# memory.net
KiCad netlist of a schematic drawn in EAGLE
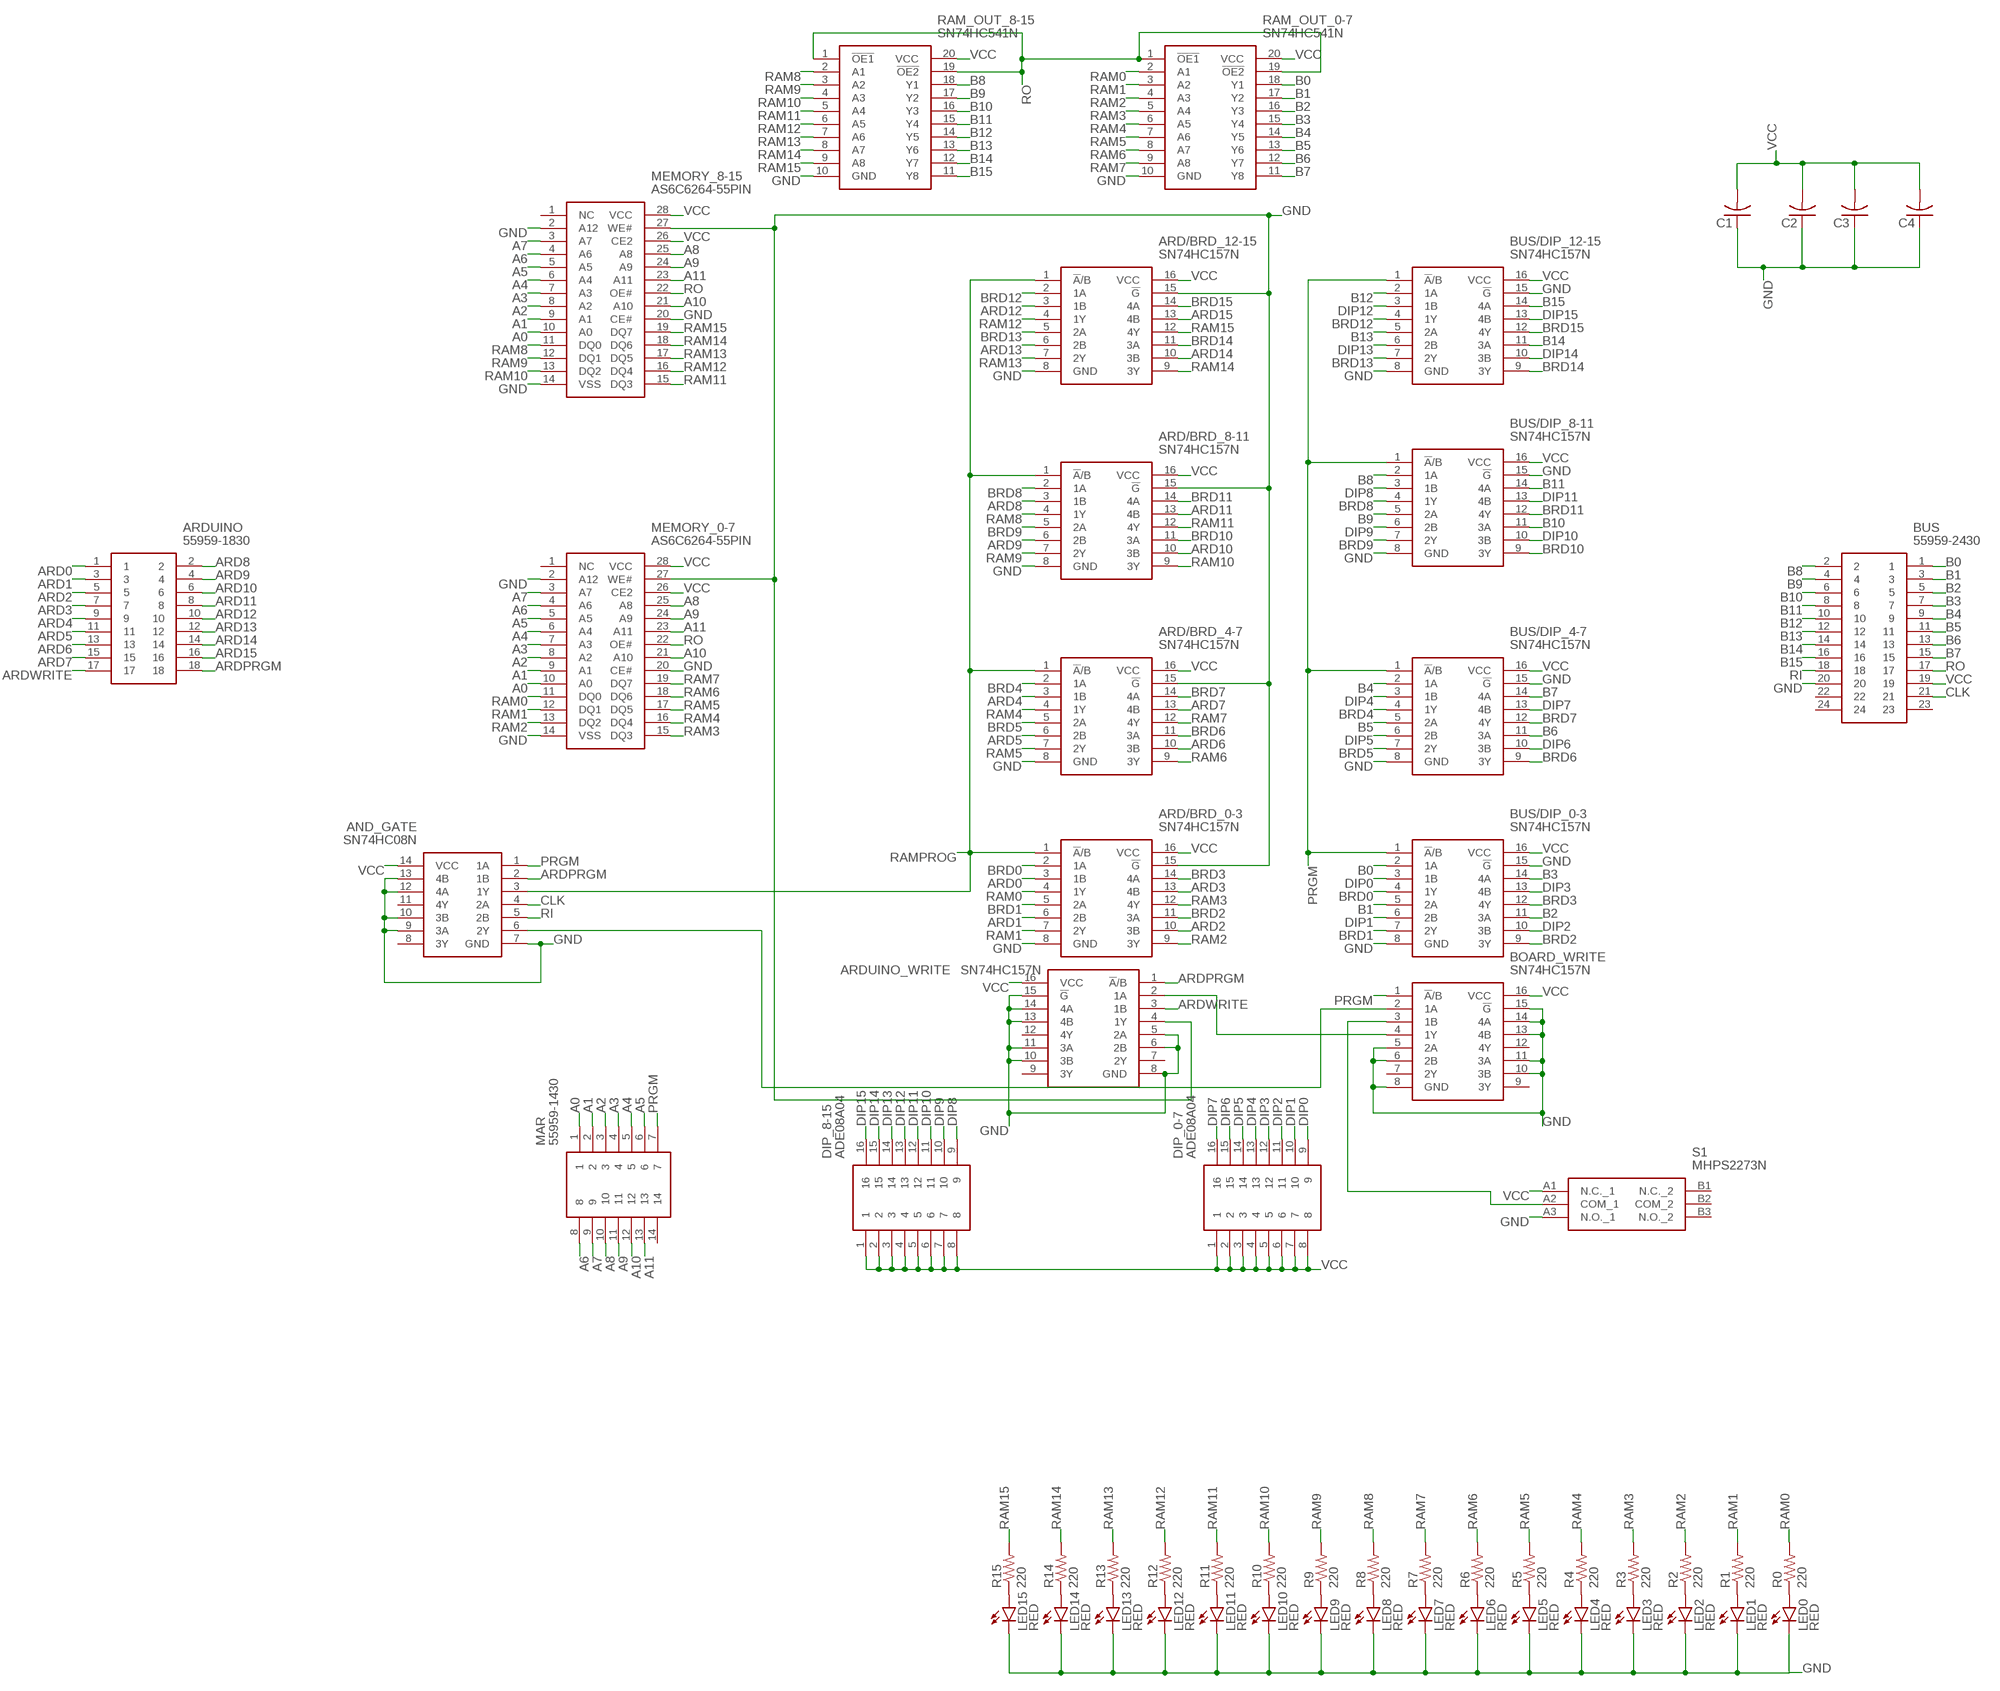
[diagram p0: schematic, sheet 1]

(export (version "E")
  (design (tool "Eeschema 10.0.6"))
  (components
    (comp (ref "AND_GATE")
      (value "SN74HC08N")
      (footprint "eagle-import:DIP794W53P254L1930H508Q14N")
      (fields (field (name "MOUSER_PART_NUMBER") "595-SN74HC08N"))
      (libsource (lib "eagle-import") (part "SN74HC08N"))
    )
    (comp (ref "ARD/BRD_0-3")
      (value "SN74HC157N")
      (footprint "eagle-import:DIP794W53P254L1930H508Q16N")
      (fields (field (name "MOUSER_PART_NUMBER") "595-SN74HC157N"))
      (libsource (lib "eagle-import") (part "SN74HC157N"))
    )
    (comp (ref "ARD/BRD_4-7")
      (value "SN74HC157N")
      (footprint "eagle-import:DIP794W53P254L1930H508Q16N")
      (fields (field (name "MOUSER_PART_NUMBER") "595-SN74HC157N"))
      (libsource (lib "eagle-import") (part "SN74HC157N"))
    )
    (comp (ref "ARD/BRD_8-11")
      (value "SN74HC157N")
      (footprint "eagle-import:DIP794W53P254L1930H508Q16N")
      (fields (field (name "MOUSER_PART_NUMBER") "595-SN74HC157N"))
      (libsource (lib "eagle-import") (part "SN74HC157N"))
    )
    (comp (ref "ARD/BRD_12-15")
      (value "SN74HC157N")
      (footprint "eagle-import:DIP794W53P254L1930H508Q16N")
      (fields (field (name "MOUSER_PART_NUMBER") "595-SN74HC157N"))
      (libsource (lib "eagle-import") (part "SN74HC157N"))
    )
    (comp (ref "ARDUINO")
      (value "55959-1830")
      (footprint "eagle-import:SHDR18W65P250X200_2X9_2140X140")
      (fields (field (name "MOUSER_PART_NUMBER") "538-55959-1830"))
      (libsource (lib "eagle-import") (part "55959-1830"))
    )
    (comp (ref "ARDUINO_WRITE")
      (value "SN74HC157N")
      (footprint "eagle-import:DIP794W53P254L1930H508Q16N")
      (fields (field (name "MOUSER_PART_NUMBER") "595-SN74HC157N"))
      (libsource (lib "eagle-import") (part "SN74HC157N"))
    )
    (comp (ref "BOARD_WRITE")
      (value "SN74HC157N")
      (footprint "eagle-import:DIP794W53P254L1930H508Q16N")
      (fields (field (name "MOUSER_PART_NUMBER") "595-SN74HC157N"))
      (libsource (lib "eagle-import") (part "SN74HC157N"))
    )
    (comp (ref "BUS")
      (value "55959-2430")
      (footprint "eagle-import:559592430")
      (fields (field (name "MOUSER_PART_NUMBER") "538-55959-2430"))
      (libsource (lib "eagle-import") (part "55959-2430"))
    )
    (comp (ref "BUS/DIP_0-3")
      (value "SN74HC157N")
      (footprint "eagle-import:DIP794W53P254L1930H508Q16N")
      (fields (field (name "MOUSER_PART_NUMBER") "595-SN74HC157N"))
      (libsource (lib "eagle-import") (part "SN74HC157N"))
    )
    (comp (ref "BUS/DIP_4-7")
      (value "SN74HC157N")
      (footprint "eagle-import:DIP794W53P254L1930H508Q16N")
      (fields (field (name "MOUSER_PART_NUMBER") "595-SN74HC157N"))
      (libsource (lib "eagle-import") (part "SN74HC157N"))
    )
    (comp (ref "BUS/DIP_8-11")
      (value "SN74HC157N")
      (footprint "eagle-import:DIP794W53P254L1930H508Q16N")
      (fields (field (name "MOUSER_PART_NUMBER") "595-SN74HC157N"))
      (libsource (lib "eagle-import") (part "SN74HC157N"))
    )
    (comp (ref "BUS/DIP_12-15")
      (value "SN74HC157N")
      (footprint "eagle-import:DIP794W53P254L1930H508Q16N")
      (fields (field (name "MOUSER_PART_NUMBER") "595-SN74HC157N"))
      (libsource (lib "eagle-import") (part "SN74HC157N"))
    )
    (comp (ref "C1")
      (value "C-US025-024X044")
      (footprint "eagle-import:C025-024X044")
      (libsource (lib "eagle-import") (part "C-US025-024X044"))
    )
    (comp (ref "C2")
      (value "C-US025-024X044")
      (footprint "eagle-import:C025-024X044")
      (libsource (lib "eagle-import") (part "C-US025-024X044"))
    )
    (comp (ref "C3")
      (value "C-US025-024X044")
      (footprint "eagle-import:C025-024X044")
      (libsource (lib "eagle-import") (part "C-US025-024X044"))
    )
    (comp (ref "C4")
      (value "C-US025-024X044")
      (footprint "eagle-import:C025-024X044")
      (libsource (lib "eagle-import") (part "C-US025-024X044"))
    )
    (comp (ref "DIP_0-7")
      (value "ADE08A04")
      (footprint "eagle-import:DIP810W60P254L2225H590Q16N")
      (fields (field (name "MOUSER_PART_NUMBER") "506-ADE08A04"))
      (libsource (lib "eagle-import") (part "ADE08A04"))
    )
    (comp (ref "DIP_8-15")
      (value "ADE08A04")
      (footprint "eagle-import:DIP810W60P254L2225H590Q16N")
      (fields (field (name "MOUSER_PART_NUMBER") "506-ADE08A04"))
      (libsource (lib "eagle-import") (part "ADE08A04"))
    )
    (comp (ref "LED0")
      (value "RED")
      (footprint "eagle-import:LED3MM")
      (libsource (lib "eagle-import") (part "LED3MM"))
    )
    (comp (ref "LED1")
      (value "RED")
      (footprint "eagle-import:LED3MM")
      (libsource (lib "eagle-import") (part "LED3MM"))
    )
    (comp (ref "LED2")
      (value "RED")
      (footprint "eagle-import:LED3MM")
      (libsource (lib "eagle-import") (part "LED3MM"))
    )
    (comp (ref "LED3")
      (value "RED")
      (footprint "eagle-import:LED3MM")
      (libsource (lib "eagle-import") (part "LED3MM"))
    )
    (comp (ref "LED4")
      (value "RED")
      (footprint "eagle-import:LED3MM")
      (libsource (lib "eagle-import") (part "LED3MM"))
    )
    (comp (ref "LED5")
      (value "RED")
      (footprint "eagle-import:LED3MM")
      (libsource (lib "eagle-import") (part "LED3MM"))
    )
    (comp (ref "LED6")
      (value "RED")
      (footprint "eagle-import:LED3MM")
      (libsource (lib "eagle-import") (part "LED3MM"))
    )
    (comp (ref "LED7")
      (value "RED")
      (footprint "eagle-import:LED3MM")
      (libsource (lib "eagle-import") (part "LED3MM"))
    )
    (comp (ref "LED8")
      (value "RED")
      (footprint "eagle-import:LED3MM")
      (libsource (lib "eagle-import") (part "LED3MM"))
    )
    (comp (ref "LED9")
      (value "RED")
      (footprint "eagle-import:LED3MM")
      (libsource (lib "eagle-import") (part "LED3MM"))
    )
    (comp (ref "LED10")
      (value "RED")
      (footprint "eagle-import:LED3MM")
      (libsource (lib "eagle-import") (part "LED3MM"))
    )
    (comp (ref "LED11")
      (value "RED")
      (footprint "eagle-import:LED3MM")
      (libsource (lib "eagle-import") (part "LED3MM"))
    )
    (comp (ref "LED12")
      (value "RED")
      (footprint "eagle-import:LED3MM")
      (libsource (lib "eagle-import") (part "LED3MM"))
    )
    (comp (ref "LED13")
      (value "RED")
      (footprint "eagle-import:LED3MM")
      (libsource (lib "eagle-import") (part "LED3MM"))
    )
    (comp (ref "LED14")
      (value "RED")
      (footprint "eagle-import:LED3MM")
      (libsource (lib "eagle-import") (part "LED3MM"))
    )
    (comp (ref "LED15")
      (value "RED")
      (footprint "eagle-import:LED3MM")
      (libsource (lib "eagle-import") (part "LED3MM"))
    )
    (comp (ref "MAR")
      (value "55959-1430")
      (footprint "eagle-import:559591430")
      (fields (field (name "MOUSER_PART_NUMBER") "538-55959-1430"))
      (libsource (lib "eagle-import") (part "55959-1430"))
    )
    (comp (ref "MEMORY_0-7")
      (value "AS6C6264-55PIN")
      (footprint "eagle-import:DIP1524W51P254L3632H394Q28N")
      (fields (field (name "MOUSER_PART_NUMBER") "913-AS6C6264-55PIN"))
      (libsource (lib "eagle-import") (part "AS6C6264-55PIN"))
    )
    (comp (ref "MEMORY_8-15")
      (value "AS6C6264-55PIN")
      (footprint "eagle-import:DIP1524W51P254L3632H394Q28N")
      (fields (field (name "MOUSER_PART_NUMBER") "913-AS6C6264-55PIN"))
      (libsource (lib "eagle-import") (part "AS6C6264-55PIN"))
    )
    (comp (ref "R0")
      (value "220")
      (footprint "eagle-import:0204_7")
      (libsource (lib "eagle-import") (part "R-US_0204/7"))
    )
    (comp (ref "R1")
      (value "220")
      (footprint "eagle-import:0204_7")
      (libsource (lib "eagle-import") (part "R-US_0204/7"))
    )
    (comp (ref "R2")
      (value "220")
      (footprint "eagle-import:0204_7")
      (libsource (lib "eagle-import") (part "R-US_0204/7"))
    )
    (comp (ref "R3")
      (value "220")
      (footprint "eagle-import:0204_7")
      (libsource (lib "eagle-import") (part "R-US_0204/7"))
    )
    (comp (ref "R4")
      (value "220")
      (footprint "eagle-import:0204_7")
      (libsource (lib "eagle-import") (part "R-US_0204/7"))
    )
    (comp (ref "R5")
      (value "220")
      (footprint "eagle-import:0204_7")
      (libsource (lib "eagle-import") (part "R-US_0204/7"))
    )
    (comp (ref "R6")
      (value "220")
      (footprint "eagle-import:0204_7")
      (libsource (lib "eagle-import") (part "R-US_0204/7"))
    )
    (comp (ref "R7")
      (value "220")
      (footprint "eagle-import:0204_7")
      (libsource (lib "eagle-import") (part "R-US_0204/7"))
    )
    (comp (ref "R8")
      (value "220")
      (footprint "eagle-import:0204_7")
      (libsource (lib "eagle-import") (part "R-US_0204/7"))
    )
    (comp (ref "R9")
      (value "220")
      (footprint "eagle-import:0204_7")
      (libsource (lib "eagle-import") (part "R-US_0204/7"))
    )
    (comp (ref "R10")
      (value "220")
      (footprint "eagle-import:0204_7")
      (libsource (lib "eagle-import") (part "R-US_0204/7"))
    )
    (comp (ref "R11")
      (value "220")
      (footprint "eagle-import:0204_7")
      (libsource (lib "eagle-import") (part "R-US_0204/7"))
    )
    (comp (ref "R12")
      (value "220")
      (footprint "eagle-import:0204_7")
      (libsource (lib "eagle-import") (part "R-US_0204/7"))
    )
    (comp (ref "R13")
      (value "220")
      (footprint "eagle-import:0204_7")
      (libsource (lib "eagle-import") (part "R-US_0204/7"))
    )
    (comp (ref "R14")
      (value "220")
      (footprint "eagle-import:0204_7")
      (libsource (lib "eagle-import") (part "R-US_0204/7"))
    )
    (comp (ref "R15")
      (value "220")
      (footprint "eagle-import:0204_7")
      (libsource (lib "eagle-import") (part "R-US_0204/7"))
    )
    (comp (ref "RAM_OUT_0-7")
      (value "SN74HC541N")
      (footprint "eagle-import:DIP794W53P254L2540H508Q20N")
      (fields (field (name "MOUSER_PART_NUMBER") "595-SN74HC541N"))
      (libsource (lib "eagle-import") (part "SN74HC541N"))
    )
    (comp (ref "RAM_OUT_8-15")
      (value "SN74HC541N")
      (footprint "eagle-import:DIP794W53P254L2540H508Q20N")
      (fields (field (name "MOUSER_PART_NUMBER") "595-SN74HC541N"))
      (libsource (lib "eagle-import") (part "SN74HC541N"))
    )
    (comp (ref "S1")
      (value "MHPS2273N")
      (footprint "eagle-import:MHPS2273N")
      (fields (field (name "MOUSER_PART_NUMBER") "642-MHPS2273N"))
      (libsource (lib "eagle-import") (part "MHPS2273N"))
    )
  )
  (nets
    (net (code "1") (name "/A0") (class "Default")
      (node (ref "MAR") (pin "1") (pinfunction "1_1") (pintype "bidirectional"))
      (node (ref "MEMORY_0-7") (pin "10") (pinfunction "A0_10") (pintype "bidirectional"))
      (node (ref "MEMORY_8-15") (pin "10") (pinfunction "A0_10") (pintype "bidirectional"))
    )
    (net (code "2") (name "/A1") (class "Default")
      (node (ref "MAR") (pin "2") (pinfunction "2_2") (pintype "bidirectional"))
      (node (ref "MEMORY_0-7") (pin "9") (pinfunction "A1_9") (pintype "bidirectional"))
      (node (ref "MEMORY_8-15") (pin "9") (pinfunction "A1_9") (pintype "bidirectional"))
    )
    (net (code "3") (name "/A2") (class "Default")
      (node (ref "MAR") (pin "3") (pinfunction "3_3") (pintype "bidirectional"))
      (node (ref "MEMORY_0-7") (pin "8") (pinfunction "A2_8") (pintype "bidirectional"))
      (node (ref "MEMORY_8-15") (pin "8") (pinfunction "A2_8") (pintype "bidirectional"))
    )
    (net (code "4") (name "/A3") (class "Default")
      (node (ref "MAR") (pin "4") (pinfunction "4_4") (pintype "bidirectional"))
      (node (ref "MEMORY_0-7") (pin "7") (pinfunction "A3_7") (pintype "bidirectional"))
      (node (ref "MEMORY_8-15") (pin "7") (pinfunction "A3_7") (pintype "bidirectional"))
    )
    (net (code "5") (name "/A4") (class "Default")
      (node (ref "MAR") (pin "5") (pinfunction "5_5") (pintype "bidirectional"))
      (node (ref "MEMORY_0-7") (pin "6") (pinfunction "A4_6") (pintype "bidirectional"))
      (node (ref "MEMORY_8-15") (pin "6") (pinfunction "A4_6") (pintype "bidirectional"))
    )
    (net (code "6") (name "/A5") (class "Default")
      (node (ref "MAR") (pin "6") (pinfunction "6_6") (pintype "bidirectional"))
      (node (ref "MEMORY_0-7") (pin "5") (pinfunction "A5_5") (pintype "bidirectional"))
      (node (ref "MEMORY_8-15") (pin "5") (pinfunction "A5_5") (pintype "bidirectional"))
    )
    (net (code "7") (name "/A6") (class "Default")
      (node (ref "MAR") (pin "8") (pinfunction "8_8") (pintype "bidirectional"))
      (node (ref "MEMORY_0-7") (pin "4") (pinfunction "A6_4") (pintype "bidirectional"))
      (node (ref "MEMORY_8-15") (pin "4") (pinfunction "A6_4") (pintype "bidirectional"))
    )
    (net (code "8") (name "/A7") (class "Default")
      (node (ref "MAR") (pin "9") (pinfunction "9_9") (pintype "bidirectional"))
      (node (ref "MEMORY_0-7") (pin "3") (pinfunction "A7_3") (pintype "bidirectional"))
      (node (ref "MEMORY_8-15") (pin "3") (pinfunction "A7_3") (pintype "bidirectional"))
    )
    (net (code "9") (name "/A8") (class "Default")
      (node (ref "MAR") (pin "10") (pinfunction "10_10") (pintype "bidirectional"))
      (node (ref "MEMORY_0-7") (pin "25") (pinfunction "A8_25") (pintype "bidirectional"))
      (node (ref "MEMORY_8-15") (pin "25") (pinfunction "A8_25") (pintype "bidirectional"))
    )
    (net (code "10") (name "/A9") (class "Default")
      (node (ref "MAR") (pin "11") (pinfunction "11_11") (pintype "bidirectional"))
      (node (ref "MEMORY_0-7") (pin "24") (pinfunction "A9_24") (pintype "bidirectional"))
      (node (ref "MEMORY_8-15") (pin "24") (pinfunction "A9_24") (pintype "bidirectional"))
    )
    (net (code "11") (name "/A10") (class "Default")
      (node (ref "MAR") (pin "12") (pinfunction "12_12") (pintype "bidirectional"))
      (node (ref "MEMORY_0-7") (pin "21") (pinfunction "A10_21") (pintype "bidirectional"))
      (node (ref "MEMORY_8-15") (pin "21") (pinfunction "A10_21") (pintype "bidirectional"))
    )
    (net (code "12") (name "/A11") (class "Default")
      (node (ref "MAR") (pin "13") (pinfunction "13_13") (pintype "bidirectional"))
      (node (ref "MEMORY_0-7") (pin "23") (pinfunction "A11_23") (pintype "bidirectional"))
      (node (ref "MEMORY_8-15") (pin "23") (pinfunction "A11_23") (pintype "bidirectional"))
    )
    (net (code "13") (name "/ARD0") (class "Default")
      (node (ref "ARD/BRD_0-3") (pin "3") (pinfunction "1B_3") (pintype "bidirectional"))
      (node (ref "ARDUINO") (pin "1") (pinfunction "1_1") (pintype "bidirectional"))
    )
    (net (code "14") (name "/ARD1") (class "Default")
      (node (ref "ARD/BRD_0-3") (pin "6") (pinfunction "2B_6") (pintype "bidirectional"))
      (node (ref "ARDUINO") (pin "3") (pinfunction "3_3") (pintype "bidirectional"))
    )
    (net (code "15") (name "/ARD2") (class "Default")
      (node (ref "ARD/BRD_0-3") (pin "10") (pinfunction "3B_10") (pintype "bidirectional"))
      (node (ref "ARDUINO") (pin "5") (pinfunction "5_5") (pintype "bidirectional"))
    )
    (net (code "16") (name "/ARD3") (class "Default")
      (node (ref "ARD/BRD_0-3") (pin "13") (pinfunction "4B_13") (pintype "bidirectional"))
      (node (ref "ARDUINO") (pin "7") (pinfunction "7_7") (pintype "bidirectional"))
    )
    (net (code "17") (name "/ARD4") (class "Default")
      (node (ref "ARD/BRD_4-7") (pin "3") (pinfunction "1B_3") (pintype "bidirectional"))
      (node (ref "ARDUINO") (pin "9") (pinfunction "9_9") (pintype "bidirectional"))
    )
    (net (code "18") (name "/ARD5") (class "Default")
      (node (ref "ARD/BRD_4-7") (pin "6") (pinfunction "2B_6") (pintype "bidirectional"))
      (node (ref "ARDUINO") (pin "11") (pinfunction "11_11") (pintype "bidirectional"))
    )
    (net (code "19") (name "/ARD6") (class "Default")
      (node (ref "ARD/BRD_4-7") (pin "10") (pinfunction "3B_10") (pintype "bidirectional"))
      (node (ref "ARDUINO") (pin "13") (pinfunction "13_13") (pintype "bidirectional"))
    )
    (net (code "20") (name "/ARD7") (class "Default")
      (node (ref "ARD/BRD_4-7") (pin "13") (pinfunction "4B_13") (pintype "bidirectional"))
      (node (ref "ARDUINO") (pin "15") (pinfunction "15_15") (pintype "bidirectional"))
    )
    (net (code "21") (name "/ARD8") (class "Default")
      (node (ref "ARD/BRD_8-11") (pin "3") (pinfunction "1B_3") (pintype "bidirectional"))
      (node (ref "ARDUINO") (pin "2") (pinfunction "2_2") (pintype "bidirectional"))
    )
    (net (code "22") (name "/ARD9") (class "Default")
      (node (ref "ARD/BRD_8-11") (pin "6") (pinfunction "2B_6") (pintype "bidirectional"))
      (node (ref "ARDUINO") (pin "4") (pinfunction "4_4") (pintype "bidirectional"))
    )
    (net (code "23") (name "/ARD10") (class "Default")
      (node (ref "ARD/BRD_8-11") (pin "10") (pinfunction "3B_10") (pintype "bidirectional"))
      (node (ref "ARDUINO") (pin "6") (pinfunction "6_6") (pintype "bidirectional"))
    )
    (net (code "24") (name "/ARD11") (class "Default")
      (node (ref "ARD/BRD_8-11") (pin "13") (pinfunction "4B_13") (pintype "bidirectional"))
      (node (ref "ARDUINO") (pin "8") (pinfunction "8_8") (pintype "bidirectional"))
    )
    (net (code "25") (name "/ARD12") (class "Default")
      (node (ref "ARD/BRD_12-15") (pin "3") (pinfunction "1B_3") (pintype "bidirectional"))
      (node (ref "ARDUINO") (pin "10") (pinfunction "10_10") (pintype "bidirectional"))
    )
    (net (code "26") (name "/ARD13") (class "Default")
      (node (ref "ARD/BRD_12-15") (pin "6") (pinfunction "2B_6") (pintype "bidirectional"))
      (node (ref "ARDUINO") (pin "12") (pinfunction "12_12") (pintype "bidirectional"))
    )
    (net (code "27") (name "/ARD14") (class "Default")
      (node (ref "ARD/BRD_12-15") (pin "10") (pinfunction "3B_10") (pintype "bidirectional"))
      (node (ref "ARDUINO") (pin "14") (pinfunction "14_14") (pintype "bidirectional"))
    )
    (net (code "28") (name "/ARD15") (class "Default")
      (node (ref "ARD/BRD_12-15") (pin "13") (pinfunction "4B_13") (pintype "bidirectional"))
      (node (ref "ARDUINO") (pin "16") (pinfunction "16_16") (pintype "bidirectional"))
    )
    (net (code "29") (name "/ARDPRGM") (class "Default")
      (node (ref "AND_GATE") (pin "2") (pinfunction "1B_2") (pintype "bidirectional"))
      (node (ref "ARDUINO") (pin "18") (pinfunction "18_18") (pintype "bidirectional"))
      (node (ref "ARDUINO_WRITE") (pin "1") (pinfunction "~{A}/B_1") (pintype "bidirectional"))
    )
    (net (code "30") (name "/ARDWRITE") (class "Default")
      (node (ref "ARDUINO") (pin "17") (pinfunction "17_17") (pintype "bidirectional"))
      (node (ref "ARDUINO_WRITE") (pin "3") (pinfunction "1B_3") (pintype "bidirectional"))
    )
    (net (code "31") (name "/B0") (class "Default")
      (node (ref "BUS") (pin "1") (pinfunction "1_1") (pintype "bidirectional"))
      (node (ref "BUS/DIP_0-3") (pin "2") (pinfunction "1A_2") (pintype "bidirectional"))
      (node (ref "RAM_OUT_0-7") (pin "18") (pinfunction "Y1_18") (pintype "bidirectional"))
    )
    (net (code "32") (name "/B1") (class "Default")
      (node (ref "BUS") (pin "3") (pinfunction "3_3") (pintype "bidirectional"))
      (node (ref "BUS/DIP_0-3") (pin "5") (pinfunction "2A_5") (pintype "bidirectional"))
      (node (ref "RAM_OUT_0-7") (pin "17") (pinfunction "Y2_17") (pintype "bidirectional"))
    )
    (net (code "33") (name "/B2") (class "Default")
      (node (ref "BUS") (pin "5") (pinfunction "5_5") (pintype "bidirectional"))
      (node (ref "BUS/DIP_0-3") (pin "11") (pinfunction "3A_11") (pintype "bidirectional"))
      (node (ref "RAM_OUT_0-7") (pin "16") (pinfunction "Y3_16") (pintype "bidirectional"))
    )
    (net (code "34") (name "/B3") (class "Default")
      (node (ref "BUS") (pin "7") (pinfunction "7_7") (pintype "bidirectional"))
      (node (ref "BUS/DIP_0-3") (pin "14") (pinfunction "4A_14") (pintype "bidirectional"))
      (node (ref "RAM_OUT_0-7") (pin "15") (pinfunction "Y4_15") (pintype "bidirectional"))
    )
    (net (code "35") (name "/B4") (class "Default")
      (node (ref "BUS") (pin "9") (pinfunction "9_9") (pintype "bidirectional"))
      (node (ref "BUS/DIP_4-7") (pin "2") (pinfunction "1A_2") (pintype "bidirectional"))
      (node (ref "RAM_OUT_0-7") (pin "14") (pinfunction "Y5_14") (pintype "bidirectional"))
    )
    (net (code "36") (name "/B5") (class "Default")
      (node (ref "BUS") (pin "11") (pinfunction "11_11") (pintype "bidirectional"))
      (node (ref "BUS/DIP_4-7") (pin "5") (pinfunction "2A_5") (pintype "bidirectional"))
      (node (ref "RAM_OUT_0-7") (pin "13") (pinfunction "Y6_13") (pintype "bidirectional"))
    )
    (net (code "37") (name "/B6") (class "Default")
      (node (ref "BUS") (pin "13") (pinfunction "13_13") (pintype "bidirectional"))
      (node (ref "BUS/DIP_4-7") (pin "11") (pinfunction "3A_11") (pintype "bidirectional"))
      (node (ref "RAM_OUT_0-7") (pin "12") (pinfunction "Y7_12") (pintype "bidirectional"))
    )
    (net (code "38") (name "/B7") (class "Default")
      (node (ref "BUS") (pin "15") (pinfunction "15_15") (pintype "bidirectional"))
      (node (ref "BUS/DIP_4-7") (pin "14") (pinfunction "4A_14") (pintype "bidirectional"))
      (node (ref "RAM_OUT_0-7") (pin "11") (pinfunction "Y8_11") (pintype "bidirectional"))
    )
    (net (code "39") (name "/B8") (class "Default")
      (node (ref "BUS") (pin "2") (pinfunction "2_2") (pintype "bidirectional"))
      (node (ref "BUS/DIP_8-11") (pin "2") (pinfunction "1A_2") (pintype "bidirectional"))
      (node (ref "RAM_OUT_8-15") (pin "18") (pinfunction "Y1_18") (pintype "bidirectional"))
    )
    (net (code "40") (name "/B9") (class "Default")
      (node (ref "BUS") (pin "4") (pinfunction "4_4") (pintype "bidirectional"))
      (node (ref "BUS/DIP_8-11") (pin "5") (pinfunction "2A_5") (pintype "bidirectional"))
      (node (ref "RAM_OUT_8-15") (pin "17") (pinfunction "Y2_17") (pintype "bidirectional"))
    )
    (net (code "41") (name "/B10") (class "Default")
      (node (ref "BUS") (pin "6") (pinfunction "6_6") (pintype "bidirectional"))
      (node (ref "BUS/DIP_8-11") (pin "11") (pinfunction "3A_11") (pintype "bidirectional"))
      (node (ref "RAM_OUT_8-15") (pin "16") (pinfunction "Y3_16") (pintype "bidirectional"))
    )
    (net (code "42") (name "/B11") (class "Default")
      (node (ref "BUS") (pin "8") (pinfunction "8_8") (pintype "bidirectional"))
      (node (ref "BUS/DIP_8-11") (pin "14") (pinfunction "4A_14") (pintype "bidirectional"))
      (node (ref "RAM_OUT_8-15") (pin "15") (pinfunction "Y4_15") (pintype "bidirectional"))
    )
    (net (code "43") (name "/B12") (class "Default")
      (node (ref "BUS") (pin "10") (pinfunction "10_10") (pintype "bidirectional"))
      (node (ref "BUS/DIP_12-15") (pin "2") (pinfunction "1A_2") (pintype "bidirectional"))
      (node (ref "RAM_OUT_8-15") (pin "14") (pinfunction "Y5_14") (pintype "bidirectional"))
    )
    (net (code "44") (name "/B13") (class "Default")
      (node (ref "BUS") (pin "12") (pinfunction "12_12") (pintype "bidirectional"))
      (node (ref "BUS/DIP_12-15") (pin "5") (pinfunction "2A_5") (pintype "bidirectional"))
      (node (ref "RAM_OUT_8-15") (pin "13") (pinfunction "Y6_13") (pintype "bidirectional"))
    )
    (net (code "45") (name "/B14") (class "Default")
      (node (ref "BUS") (pin "14") (pinfunction "14_14") (pintype "bidirectional"))
      (node (ref "BUS/DIP_12-15") (pin "11") (pinfunction "3A_11") (pintype "bidirectional"))
      (node (ref "RAM_OUT_8-15") (pin "12") (pinfunction "Y7_12") (pintype "bidirectional"))
    )
    (net (code "46") (name "/B15") (class "Default")
      (node (ref "BUS") (pin "16") (pinfunction "16_16") (pintype "bidirectional"))
      (node (ref "BUS/DIP_12-15") (pin "14") (pinfunction "4A_14") (pintype "bidirectional"))
      (node (ref "RAM_OUT_8-15") (pin "11") (pinfunction "Y8_11") (pintype "bidirectional"))
    )
    (net (code "47") (name "/BRD0") (class "Default")
      (node (ref "ARD/BRD_0-3") (pin "2") (pinfunction "1A_2") (pintype "bidirectional"))
      (node (ref "BUS/DIP_0-3") (pin "4") (pinfunction "1Y_4") (pintype "bidirectional"))
    )
    (net (code "48") (name "/BRD1") (class "Default")
      (node (ref "ARD/BRD_0-3") (pin "5") (pinfunction "2A_5") (pintype "bidirectional"))
      (node (ref "BUS/DIP_0-3") (pin "7") (pinfunction "2Y_7") (pintype "bidirectional"))
    )
    (net (code "49") (name "/BRD2") (class "Default")
      (node (ref "ARD/BRD_0-3") (pin "11") (pinfunction "3A_11") (pintype "bidirectional"))
      (node (ref "BUS/DIP_0-3") (pin "9") (pinfunction "3Y_9") (pintype "bidirectional"))
    )
    (net (code "50") (name "/BRD3") (class "Default")
      (node (ref "ARD/BRD_0-3") (pin "14") (pinfunction "4A_14") (pintype "bidirectional"))
      (node (ref "BUS/DIP_0-3") (pin "12") (pinfunction "4Y_12") (pintype "bidirectional"))
    )
    (net (code "51") (name "/BRD4") (class "Default")
      (node (ref "ARD/BRD_4-7") (pin "2") (pinfunction "1A_2") (pintype "bidirectional"))
      (node (ref "BUS/DIP_4-7") (pin "4") (pinfunction "1Y_4") (pintype "bidirectional"))
    )
    (net (code "52") (name "/BRD5") (class "Default")
      (node (ref "ARD/BRD_4-7") (pin "5") (pinfunction "2A_5") (pintype "bidirectional"))
      (node (ref "BUS/DIP_4-7") (pin "7") (pinfunction "2Y_7") (pintype "bidirectional"))
    )
    (net (code "53") (name "/BRD6") (class "Default")
      (node (ref "ARD/BRD_4-7") (pin "11") (pinfunction "3A_11") (pintype "bidirectional"))
      (node (ref "BUS/DIP_4-7") (pin "9") (pinfunction "3Y_9") (pintype "bidirectional"))
    )
    (net (code "54") (name "/BRD7") (class "Default")
      (node (ref "ARD/BRD_4-7") (pin "14") (pinfunction "4A_14") (pintype "bidirectional"))
      (node (ref "BUS/DIP_4-7") (pin "12") (pinfunction "4Y_12") (pintype "bidirectional"))
    )
    (net (code "55") (name "/BRD8") (class "Default")
      (node (ref "ARD/BRD_8-11") (pin "2") (pinfunction "1A_2") (pintype "bidirectional"))
      (node (ref "BUS/DIP_8-11") (pin "4") (pinfunction "1Y_4") (pintype "bidirectional"))
    )
    (net (code "56") (name "/BRD9") (class "Default")
      (node (ref "ARD/BRD_8-11") (pin "5") (pinfunction "2A_5") (pintype "bidirectional"))
      (node (ref "BUS/DIP_8-11") (pin "7") (pinfunction "2Y_7") (pintype "bidirectional"))
    )
    (net (code "57") (name "/BRD10") (class "Default")
      (node (ref "ARD/BRD_8-11") (pin "11") (pinfunction "3A_11") (pintype "bidirectional"))
      (node (ref "BUS/DIP_8-11") (pin "9") (pinfunction "3Y_9") (pintype "bidirectional"))
    )
    (net (code "58") (name "/BRD11") (class "Default")
      (node (ref "ARD/BRD_8-11") (pin "14") (pinfunction "4A_14") (pintype "bidirectional"))
      (node (ref "BUS/DIP_8-11") (pin "12") (pinfunction "4Y_12") (pintype "bidirectional"))
    )
    (net (code "59") (name "/BRD12") (class "Default")
      (node (ref "ARD/BRD_12-15") (pin "2") (pinfunction "1A_2") (pintype "bidirectional"))
      (node (ref "BUS/DIP_12-15") (pin "4") (pinfunction "1Y_4") (pintype "bidirectional"))
    )
    (net (code "60") (name "/BRD13") (class "Default")
      (node (ref "ARD/BRD_12-15") (pin "5") (pinfunction "2A_5") (pintype "bidirectional"))
      (node (ref "BUS/DIP_12-15") (pin "7") (pinfunction "2Y_7") (pintype "bidirectional"))
    )
    (net (code "61") (name "/BRD14") (class "Default")
      (node (ref "ARD/BRD_12-15") (pin "11") (pinfunction "3A_11") (pintype "bidirectional"))
      (node (ref "BUS/DIP_12-15") (pin "9") (pinfunction "3Y_9") (pintype "bidirectional"))
    )
    (net (code "62") (name "/BRD15") (class "Default")
      (node (ref "ARD/BRD_12-15") (pin "14") (pinfunction "4A_14") (pintype "bidirectional"))
      (node (ref "BUS/DIP_12-15") (pin "12") (pinfunction "4Y_12") (pintype "bidirectional"))
    )
    (net (code "63") (name "/CLK") (class "Default")
      (node (ref "AND_GATE") (pin "4") (pinfunction "2A_4") (pintype "bidirectional"))
      (node (ref "BUS") (pin "21") (pinfunction "21_21") (pintype "bidirectional"))
    )
    (net (code "64") (name "/DIP0") (class "Default")
      (node (ref "BUS/DIP_0-3") (pin "3") (pinfunction "1B_3") (pintype "bidirectional"))
      (node (ref "DIP_0-7") (pin "9") (pinfunction "9_9") (pintype "bidirectional"))
    )
    (net (code "65") (name "/DIP1") (class "Default")
      (node (ref "BUS/DIP_0-3") (pin "6") (pinfunction "2B_6") (pintype "bidirectional"))
      (node (ref "DIP_0-7") (pin "10") (pinfunction "10_10") (pintype "bidirectional"))
    )
    (net (code "66") (name "/DIP2") (class "Default")
      (node (ref "BUS/DIP_0-3") (pin "10") (pinfunction "3B_10") (pintype "bidirectional"))
      (node (ref "DIP_0-7") (pin "11") (pinfunction "11_11") (pintype "bidirectional"))
    )
    (net (code "67") (name "/DIP3") (class "Default")
      (node (ref "BUS/DIP_0-3") (pin "13") (pinfunction "4B_13") (pintype "bidirectional"))
      (node (ref "DIP_0-7") (pin "12") (pinfunction "12_12") (pintype "bidirectional"))
    )
    (net (code "68") (name "/DIP4") (class "Default")
      (node (ref "BUS/DIP_4-7") (pin "3") (pinfunction "1B_3") (pintype "bidirectional"))
      (node (ref "DIP_0-7") (pin "13") (pinfunction "13_13") (pintype "bidirectional"))
    )
    (net (code "69") (name "/DIP5") (class "Default")
      (node (ref "BUS/DIP_4-7") (pin "6") (pinfunction "2B_6") (pintype "bidirectional"))
      (node (ref "DIP_0-7") (pin "14") (pinfunction "14_14") (pintype "bidirectional"))
    )
    (net (code "70") (name "/DIP6") (class "Default")
      (node (ref "BUS/DIP_4-7") (pin "10") (pinfunction "3B_10") (pintype "bidirectional"))
      (node (ref "DIP_0-7") (pin "15") (pinfunction "15_15") (pintype "bidirectional"))
    )
    (net (code "71") (name "/DIP7") (class "Default")
      (node (ref "BUS/DIP_4-7") (pin "13") (pinfunction "4B_13") (pintype "bidirectional"))
      (node (ref "DIP_0-7") (pin "16") (pinfunction "16_16") (pintype "bidirectional"))
    )
    (net (code "72") (name "/DIP8") (class "Default")
      (node (ref "BUS/DIP_8-11") (pin "3") (pinfunction "1B_3") (pintype "bidirectional"))
      (node (ref "DIP_8-15") (pin "9") (pinfunction "9_9") (pintype "bidirectional"))
    )
    (net (code "73") (name "/DIP9") (class "Default")
      (node (ref "BUS/DIP_8-11") (pin "6") (pinfunction "2B_6") (pintype "bidirectional"))
      (node (ref "DIP_8-15") (pin "10") (pinfunction "10_10") (pintype "bidirectional"))
    )
    (net (code "74") (name "/DIP10") (class "Default")
      (node (ref "BUS/DIP_8-11") (pin "10") (pinfunction "3B_10") (pintype "bidirectional"))
      (node (ref "DIP_8-15") (pin "11") (pinfunction "11_11") (pintype "bidirectional"))
    )
    (net (code "75") (name "/DIP11") (class "Default")
      (node (ref "BUS/DIP_8-11") (pin "13") (pinfunction "4B_13") (pintype "bidirectional"))
      (node (ref "DIP_8-15") (pin "12") (pinfunction "12_12") (pintype "bidirectional"))
    )
    (net (code "76") (name "/DIP12") (class "Default")
      (node (ref "BUS/DIP_12-15") (pin "3") (pinfunction "1B_3") (pintype "bidirectional"))
      (node (ref "DIP_8-15") (pin "13") (pinfunction "13_13") (pintype "bidirectional"))
    )
    (net (code "77") (name "/DIP13") (class "Default")
      (node (ref "BUS/DIP_12-15") (pin "6") (pinfunction "2B_6") (pintype "bidirectional"))
      (node (ref "DIP_8-15") (pin "14") (pinfunction "14_14") (pintype "bidirectional"))
    )
    (net (code "78") (name "/DIP14") (class "Default")
      (node (ref "BUS/DIP_12-15") (pin "10") (pinfunction "3B_10") (pintype "bidirectional"))
      (node (ref "DIP_8-15") (pin "15") (pinfunction "15_15") (pintype "bidirectional"))
    )
    (net (code "79") (name "/DIP15") (class "Default")
      (node (ref "BUS/DIP_12-15") (pin "13") (pinfunction "4B_13") (pintype "bidirectional"))
      (node (ref "DIP_8-15") (pin "16") (pinfunction "16_16") (pintype "bidirectional"))
    )
    (net (code "80") (name "/GND") (class "Default")
      (node (ref "AND_GATE") (pin "10") (pinfunction "3B_10") (pintype "bidirectional"))
      (node (ref "AND_GATE") (pin "12") (pinfunction "4A_12") (pintype "bidirectional"))
      (node (ref "AND_GATE") (pin "13") (pinfunction "4B_13") (pintype "bidirectional"))
      (node (ref "AND_GATE") (pin "7") (pinfunction "GND_7") (pintype "bidirectional"))
      (node (ref "AND_GATE") (pin "9") (pinfunction "3A_9") (pintype "bidirectional"))
      (node (ref "ARD/BRD_0-3") (pin "15") (pinfunction "~{G}_15") (pintype "bidirectional"))
      (node (ref "ARD/BRD_0-3") (pin "8") (pinfunction "GND_8") (pintype "bidirectional"))
      (node (ref "ARD/BRD_12-15") (pin "15") (pinfunction "~{G}_15") (pintype "bidirectional"))
      (node (ref "ARD/BRD_12-15") (pin "8") (pinfunction "GND_8") (pintype "bidirectional"))
      (node (ref "ARD/BRD_4-7") (pin "15") (pinfunction "~{G}_15") (pintype "bidirectional"))
      (node (ref "ARD/BRD_4-7") (pin "8") (pinfunction "GND_8") (pintype "bidirectional"))
      (node (ref "ARD/BRD_8-11") (pin "15") (pinfunction "~{G}_15") (pintype "bidirectional"))
      (node (ref "ARD/BRD_8-11") (pin "8") (pinfunction "GND_8") (pintype "bidirectional"))
      (node (ref "ARDUINO_WRITE") (pin "10") (pinfunction "3B_10") (pintype "bidirectional"))
      (node (ref "ARDUINO_WRITE") (pin "11") (pinfunction "3A_11") (pintype "bidirectional"))
      (node (ref "ARDUINO_WRITE") (pin "13") (pinfunction "4B_13") (pintype "bidirectional"))
      (node (ref "ARDUINO_WRITE") (pin "14") (pinfunction "4A_14") (pintype "bidirectional"))
      (node (ref "ARDUINO_WRITE") (pin "15") (pinfunction "~{G}_15") (pintype "bidirectional"))
      (node (ref "ARDUINO_WRITE") (pin "4") (pinfunction "1Y_4") (pintype "bidirectional"))
      (node (ref "ARDUINO_WRITE") (pin "5") (pinfunction "2A_5") (pintype "bidirectional"))
      (node (ref "ARDUINO_WRITE") (pin "6") (pinfunction "2B_6") (pintype "bidirectional"))
      (node (ref "ARDUINO_WRITE") (pin "8") (pinfunction "GND_8") (pintype "bidirectional"))
      (node (ref "BOARD_WRITE") (pin "10") (pinfunction "3B_10") (pintype "bidirectional"))
      (node (ref "BOARD_WRITE") (pin "11") (pinfunction "3A_11") (pintype "bidirectional"))
      (node (ref "BOARD_WRITE") (pin "13") (pinfunction "4B_13") (pintype "bidirectional"))
      (node (ref "BOARD_WRITE") (pin "14") (pinfunction "4A_14") (pintype "bidirectional"))
      (node (ref "BOARD_WRITE") (pin "15") (pinfunction "~{G}_15") (pintype "bidirectional"))
      (node (ref "BOARD_WRITE") (pin "5") (pinfunction "2A_5") (pintype "bidirectional"))
      (node (ref "BOARD_WRITE") (pin "6") (pinfunction "2B_6") (pintype "bidirectional"))
      (node (ref "BOARD_WRITE") (pin "8") (pinfunction "GND_8") (pintype "bidirectional"))
      (node (ref "BUS") (pin "20") (pinfunction "20_20") (pintype "bidirectional"))
      (node (ref "BUS/DIP_0-3") (pin "15") (pinfunction "~{G}_15") (pintype "bidirectional"))
      (node (ref "BUS/DIP_0-3") (pin "8") (pinfunction "GND_8") (pintype "bidirectional"))
      (node (ref "BUS/DIP_12-15") (pin "15") (pinfunction "~{G}_15") (pintype "bidirectional"))
      (node (ref "BUS/DIP_12-15") (pin "8") (pinfunction "GND_8") (pintype "bidirectional"))
      (node (ref "BUS/DIP_4-7") (pin "15") (pinfunction "~{G}_15") (pintype "bidirectional"))
      (node (ref "BUS/DIP_4-7") (pin "8") (pinfunction "GND_8") (pintype "bidirectional"))
      (node (ref "BUS/DIP_8-11") (pin "15") (pinfunction "~{G}_15") (pintype "bidirectional"))
      (node (ref "BUS/DIP_8-11") (pin "8") (pinfunction "GND_8") (pintype "bidirectional"))
      (node (ref "C1") (pin "1") (pinfunction "1_1") (pintype "passive"))
      (node (ref "C2") (pin "1") (pinfunction "1_1") (pintype "passive"))
      (node (ref "C3") (pin "1") (pinfunction "1_1") (pintype "passive"))
      (node (ref "C4") (pin "1") (pinfunction "1_1") (pintype "passive"))
      (node (ref "LED0") (pin "K") (pinfunction "C_K") (pintype "passive"))
      (node (ref "LED1") (pin "K") (pinfunction "C_K") (pintype "passive"))
      (node (ref "LED10") (pin "K") (pinfunction "C_K") (pintype "passive"))
      (node (ref "LED11") (pin "K") (pinfunction "C_K") (pintype "passive"))
      (node (ref "LED12") (pin "K") (pinfunction "C_K") (pintype "passive"))
      (node (ref "LED13") (pin "K") (pinfunction "C_K") (pintype "passive"))
      (node (ref "LED14") (pin "K") (pinfunction "C_K") (pintype "passive"))
      (node (ref "LED15") (pin "K") (pinfunction "C_K") (pintype "passive"))
      (node (ref "LED2") (pin "K") (pinfunction "C_K") (pintype "passive"))
      (node (ref "LED3") (pin "K") (pinfunction "C_K") (pintype "passive"))
      (node (ref "LED4") (pin "K") (pinfunction "C_K") (pintype "passive"))
      (node (ref "LED5") (pin "K") (pinfunction "C_K") (pintype "passive"))
      (node (ref "LED6") (pin "K") (pinfunction "C_K") (pintype "passive"))
      (node (ref "LED7") (pin "K") (pinfunction "C_K") (pintype "passive"))
      (node (ref "LED8") (pin "K") (pinfunction "C_K") (pintype "passive"))
      (node (ref "LED9") (pin "K") (pinfunction "C_K") (pintype "passive"))
      (node (ref "MEMORY_0-7") (pin "14") (pinfunction "VSS_14") (pintype "bidirectional"))
      (node (ref "MEMORY_0-7") (pin "2") (pinfunction "A12_2") (pintype "bidirectional"))
      (node (ref "MEMORY_0-7") (pin "20") (pinfunction "CE#_20") (pintype "bidirectional"))
      (node (ref "MEMORY_0-7") (pin "27") (pinfunction "WE#_27") (pintype "bidirectional"))
      (node (ref "MEMORY_8-15") (pin "14") (pinfunction "VSS_14") (pintype "bidirectional"))
      (node (ref "MEMORY_8-15") (pin "2") (pinfunction "A12_2") (pintype "bidirectional"))
      (node (ref "MEMORY_8-15") (pin "20") (pinfunction "CE#_20") (pintype "bidirectional"))
      (node (ref "MEMORY_8-15") (pin "27") (pinfunction "WE#_27") (pintype "bidirectional"))
      (node (ref "RAM_OUT_0-7") (pin "10") (pinfunction "GND_10") (pintype "bidirectional"))
      (node (ref "RAM_OUT_8-15") (pin "10") (pinfunction "GND_10") (pintype "bidirectional"))
      (node (ref "S1") (pin "A3") (pinfunction "N.O._1_A3") (pintype "bidirectional"))
    )
    (net (code "81") (name "/PRGM") (class "Default")
      (node (ref "AND_GATE") (pin "1") (pinfunction "1A_1") (pintype "bidirectional"))
      (node (ref "BOARD_WRITE") (pin "1") (pinfunction "~{A}/B_1") (pintype "bidirectional"))
      (node (ref "BUS/DIP_0-3") (pin "1") (pinfunction "~{A}/B_1") (pintype "bidirectional"))
      (node (ref "BUS/DIP_12-15") (pin "1") (pinfunction "~{A}/B_1") (pintype "bidirectional"))
      (node (ref "BUS/DIP_4-7") (pin "1") (pinfunction "~{A}/B_1") (pintype "bidirectional"))
      (node (ref "BUS/DIP_8-11") (pin "1") (pinfunction "~{A}/B_1") (pintype "bidirectional"))
      (node (ref "MAR") (pin "7") (pinfunction "7_7") (pintype "bidirectional"))
    )
    (net (code "82") (name "/RAM0") (class "Default")
      (node (ref "ARD/BRD_0-3") (pin "4") (pinfunction "1Y_4") (pintype "bidirectional"))
      (node (ref "MEMORY_0-7") (pin "11") (pinfunction "DQ0_11") (pintype "bidirectional"))
      (node (ref "R0") (pin "2") (pinfunction "2_2") (pintype "passive"))
      (node (ref "RAM_OUT_0-7") (pin "2") (pinfunction "A1_2") (pintype "bidirectional"))
    )
    (net (code "83") (name "/RAM1") (class "Default")
      (node (ref "ARD/BRD_0-3") (pin "7") (pinfunction "2Y_7") (pintype "bidirectional"))
      (node (ref "MEMORY_0-7") (pin "12") (pinfunction "DQ1_12") (pintype "bidirectional"))
      (node (ref "R1") (pin "2") (pinfunction "2_2") (pintype "passive"))
      (node (ref "RAM_OUT_0-7") (pin "3") (pinfunction "A2_3") (pintype "bidirectional"))
    )
    (net (code "84") (name "/RAM2") (class "Default")
      (node (ref "ARD/BRD_0-3") (pin "9") (pinfunction "3Y_9") (pintype "bidirectional"))
      (node (ref "MEMORY_0-7") (pin "13") (pinfunction "DQ2_13") (pintype "bidirectional"))
      (node (ref "R2") (pin "2") (pinfunction "2_2") (pintype "passive"))
      (node (ref "RAM_OUT_0-7") (pin "4") (pinfunction "A3_4") (pintype "bidirectional"))
    )
    (net (code "85") (name "/RAM3") (class "Default")
      (node (ref "ARD/BRD_0-3") (pin "12") (pinfunction "4Y_12") (pintype "bidirectional"))
      (node (ref "MEMORY_0-7") (pin "15") (pinfunction "DQ3_15") (pintype "bidirectional"))
      (node (ref "R3") (pin "2") (pinfunction "2_2") (pintype "passive"))
      (node (ref "RAM_OUT_0-7") (pin "5") (pinfunction "A4_5") (pintype "bidirectional"))
    )
    (net (code "86") (name "/RAM4") (class "Default")
      (node (ref "ARD/BRD_4-7") (pin "4") (pinfunction "1Y_4") (pintype "bidirectional"))
      (node (ref "MEMORY_0-7") (pin "16") (pinfunction "DQ4_16") (pintype "bidirectional"))
      (node (ref "R4") (pin "2") (pinfunction "2_2") (pintype "passive"))
      (node (ref "RAM_OUT_0-7") (pin "6") (pinfunction "A5_6") (pintype "bidirectional"))
    )
    (net (code "87") (name "/RAM5") (class "Default")
      (node (ref "ARD/BRD_4-7") (pin "7") (pinfunction "2Y_7") (pintype "bidirectional"))
      (node (ref "MEMORY_0-7") (pin "17") (pinfunction "DQ5_17") (pintype "bidirectional"))
      (node (ref "R5") (pin "2") (pinfunction "2_2") (pintype "passive"))
      (node (ref "RAM_OUT_0-7") (pin "7") (pinfunction "A6_7") (pintype "bidirectional"))
    )
    (net (code "88") (name "/RAM6") (class "Default")
      (node (ref "ARD/BRD_4-7") (pin "9") (pinfunction "3Y_9") (pintype "bidirectional"))
      (node (ref "MEMORY_0-7") (pin "18") (pinfunction "DQ6_18") (pintype "bidirectional"))
      (node (ref "R6") (pin "2") (pinfunction "2_2") (pintype "passive"))
      (node (ref "RAM_OUT_0-7") (pin "8") (pinfunction "A7_8") (pintype "bidirectional"))
    )
    (net (code "89") (name "/RAM7") (class "Default")
      (node (ref "ARD/BRD_4-7") (pin "12") (pinfunction "4Y_12") (pintype "bidirectional"))
      (node (ref "MEMORY_0-7") (pin "19") (pinfunction "DQ7_19") (pintype "bidirectional"))
      (node (ref "R7") (pin "2") (pinfunction "2_2") (pintype "passive"))
      (node (ref "RAM_OUT_0-7") (pin "9") (pinfunction "A8_9") (pintype "bidirectional"))
    )
    (net (code "90") (name "/RAM8") (class "Default")
      (node (ref "ARD/BRD_8-11") (pin "4") (pinfunction "1Y_4") (pintype "bidirectional"))
      (node (ref "MEMORY_8-15") (pin "11") (pinfunction "DQ0_11") (pintype "bidirectional"))
      (node (ref "R8") (pin "2") (pinfunction "2_2") (pintype "passive"))
      (node (ref "RAM_OUT_8-15") (pin "2") (pinfunction "A1_2") (pintype "bidirectional"))
    )
    (net (code "91") (name "/RAM9") (class "Default")
      (node (ref "ARD/BRD_8-11") (pin "7") (pinfunction "2Y_7") (pintype "bidirectional"))
      (node (ref "MEMORY_8-15") (pin "12") (pinfunction "DQ1_12") (pintype "bidirectional"))
      (node (ref "R9") (pin "2") (pinfunction "2_2") (pintype "passive"))
      (node (ref "RAM_OUT_8-15") (pin "3") (pinfunction "A2_3") (pintype "bidirectional"))
    )
    (net (code "92") (name "/RAM10") (class "Default")
      (node (ref "ARD/BRD_8-11") (pin "9") (pinfunction "3Y_9") (pintype "bidirectional"))
      (node (ref "MEMORY_8-15") (pin "13") (pinfunction "DQ2_13") (pintype "bidirectional"))
      (node (ref "R10") (pin "2") (pinfunction "2_2") (pintype "passive"))
      (node (ref "RAM_OUT_8-15") (pin "4") (pinfunction "A3_4") (pintype "bidirectional"))
    )
    (net (code "93") (name "/RAM11") (class "Default")
      (node (ref "ARD/BRD_8-11") (pin "12") (pinfunction "4Y_12") (pintype "bidirectional"))
      (node (ref "MEMORY_8-15") (pin "15") (pinfunction "DQ3_15") (pintype "bidirectional"))
      (node (ref "R11") (pin "2") (pinfunction "2_2") (pintype "passive"))
      (node (ref "RAM_OUT_8-15") (pin "5") (pinfunction "A4_5") (pintype "bidirectional"))
    )
    (net (code "94") (name "/RAM12") (class "Default")
      (node (ref "ARD/BRD_12-15") (pin "4") (pinfunction "1Y_4") (pintype "bidirectional"))
      (node (ref "MEMORY_8-15") (pin "16") (pinfunction "DQ4_16") (pintype "bidirectional"))
      (node (ref "R12") (pin "2") (pinfunction "2_2") (pintype "passive"))
      (node (ref "RAM_OUT_8-15") (pin "6") (pinfunction "A5_6") (pintype "bidirectional"))
    )
    (net (code "95") (name "/RAM13") (class "Default")
      (node (ref "ARD/BRD_12-15") (pin "7") (pinfunction "2Y_7") (pintype "bidirectional"))
      (node (ref "MEMORY_8-15") (pin "17") (pinfunction "DQ5_17") (pintype "bidirectional"))
      (node (ref "R13") (pin "2") (pinfunction "2_2") (pintype "passive"))
      (node (ref "RAM_OUT_8-15") (pin "7") (pinfunction "A6_7") (pintype "bidirectional"))
    )
    (net (code "96") (name "/RAM14") (class "Default")
      (node (ref "ARD/BRD_12-15") (pin "9") (pinfunction "3Y_9") (pintype "bidirectional"))
      (node (ref "MEMORY_8-15") (pin "18") (pinfunction "DQ6_18") (pintype "bidirectional"))
      (node (ref "R14") (pin "2") (pinfunction "2_2") (pintype "passive"))
      (node (ref "RAM_OUT_8-15") (pin "8") (pinfunction "A7_8") (pintype "bidirectional"))
    )
    (net (code "97") (name "/RAM15") (class "Default")
      (node (ref "ARD/BRD_12-15") (pin "12") (pinfunction "4Y_12") (pintype "bidirectional"))
      (node (ref "MEMORY_8-15") (pin "19") (pinfunction "DQ7_19") (pintype "bidirectional"))
      (node (ref "R15") (pin "2") (pinfunction "2_2") (pintype "passive"))
      (node (ref "RAM_OUT_8-15") (pin "9") (pinfunction "A8_9") (pintype "bidirectional"))
    )
    (net (code "98") (name "/RAMPROG") (class "Default")
      (node (ref "AND_GATE") (pin "3") (pinfunction "1Y_3") (pintype "bidirectional"))
      (node (ref "ARD/BRD_0-3") (pin "1") (pinfunction "~{A}/B_1") (pintype "bidirectional"))
      (node (ref "ARD/BRD_12-15") (pin "1") (pinfunction "~{A}/B_1") (pintype "bidirectional"))
      (node (ref "ARD/BRD_4-7") (pin "1") (pinfunction "~{A}/B_1") (pintype "bidirectional"))
      (node (ref "ARD/BRD_8-11") (pin "1") (pinfunction "~{A}/B_1") (pintype "bidirectional"))
    )
    (net (code "99") (name "/RI") (class "Default")
      (node (ref "AND_GATE") (pin "5") (pinfunction "2B_5") (pintype "bidirectional"))
      (node (ref "BUS") (pin "18") (pinfunction "18_18") (pintype "bidirectional"))
    )
    (net (code "100") (name "/RO") (class "Default")
      (node (ref "BUS") (pin "17") (pinfunction "17_17") (pintype "bidirectional"))
      (node (ref "MEMORY_0-7") (pin "22") (pinfunction "OE#_22") (pintype "bidirectional"))
      (node (ref "MEMORY_8-15") (pin "22") (pinfunction "OE#_22") (pintype "bidirectional"))
      (node (ref "RAM_OUT_0-7") (pin "1") (pinfunction "~{OE1}_1") (pintype "bidirectional"))
      (node (ref "RAM_OUT_0-7") (pin "19") (pinfunction "~{OE2}_19") (pintype "bidirectional"))
      (node (ref "RAM_OUT_8-15") (pin "1") (pinfunction "~{OE1}_1") (pintype "bidirectional"))
      (node (ref "RAM_OUT_8-15") (pin "19") (pinfunction "~{OE2}_19") (pintype "bidirectional"))
    )
    (net (code "101") (name "/VCC") (class "Default")
      (node (ref "AND_GATE") (pin "14") (pinfunction "VCC_14") (pintype "bidirectional"))
      (node (ref "ARD/BRD_0-3") (pin "16") (pinfunction "VCC_16") (pintype "bidirectional"))
      (node (ref "ARD/BRD_12-15") (pin "16") (pinfunction "VCC_16") (pintype "bidirectional"))
      (node (ref "ARD/BRD_4-7") (pin "16") (pinfunction "VCC_16") (pintype "bidirectional"))
      (node (ref "ARD/BRD_8-11") (pin "16") (pinfunction "VCC_16") (pintype "bidirectional"))
      (node (ref "ARDUINO_WRITE") (pin "16") (pinfunction "VCC_16") (pintype "bidirectional"))
      (node (ref "BOARD_WRITE") (pin "16") (pinfunction "VCC_16") (pintype "bidirectional"))
      (node (ref "BUS") (pin "19") (pinfunction "19_19") (pintype "bidirectional"))
      (node (ref "BUS/DIP_0-3") (pin "16") (pinfunction "VCC_16") (pintype "bidirectional"))
      (node (ref "BUS/DIP_12-15") (pin "16") (pinfunction "VCC_16") (pintype "bidirectional"))
      (node (ref "BUS/DIP_4-7") (pin "16") (pinfunction "VCC_16") (pintype "bidirectional"))
      (node (ref "BUS/DIP_8-11") (pin "16") (pinfunction "VCC_16") (pintype "bidirectional"))
      (node (ref "C1") (pin "2") (pinfunction "2_2") (pintype "passive"))
      (node (ref "C2") (pin "2") (pinfunction "2_2") (pintype "passive"))
      (node (ref "C3") (pin "2") (pinfunction "2_2") (pintype "passive"))
      (node (ref "C4") (pin "2") (pinfunction "2_2") (pintype "passive"))
      (node (ref "DIP_0-7") (pin "1") (pinfunction "1_1") (pintype "bidirectional"))
      (node (ref "DIP_0-7") (pin "2") (pinfunction "2_2") (pintype "bidirectional"))
      (node (ref "DIP_0-7") (pin "3") (pinfunction "3_3") (pintype "bidirectional"))
      (node (ref "DIP_0-7") (pin "4") (pinfunction "4_4") (pintype "bidirectional"))
      (node (ref "DIP_0-7") (pin "5") (pinfunction "5_5") (pintype "bidirectional"))
      (node (ref "DIP_0-7") (pin "6") (pinfunction "6_6") (pintype "bidirectional"))
      (node (ref "DIP_0-7") (pin "7") (pinfunction "7_7") (pintype "bidirectional"))
      (node (ref "DIP_0-7") (pin "8") (pinfunction "8_8") (pintype "bidirectional"))
      (node (ref "DIP_8-15") (pin "1") (pinfunction "1_1") (pintype "bidirectional"))
      (node (ref "DIP_8-15") (pin "2") (pinfunction "2_2") (pintype "bidirectional"))
      (node (ref "DIP_8-15") (pin "3") (pinfunction "3_3") (pintype "bidirectional"))
      (node (ref "DIP_8-15") (pin "4") (pinfunction "4_4") (pintype "bidirectional"))
      (node (ref "DIP_8-15") (pin "5") (pinfunction "5_5") (pintype "bidirectional"))
      (node (ref "DIP_8-15") (pin "6") (pinfunction "6_6") (pintype "bidirectional"))
      (node (ref "DIP_8-15") (pin "7") (pinfunction "7_7") (pintype "bidirectional"))
      (node (ref "DIP_8-15") (pin "8") (pinfunction "8_8") (pintype "bidirectional"))
      (node (ref "MEMORY_0-7") (pin "26") (pinfunction "CE2_26") (pintype "bidirectional"))
      (node (ref "MEMORY_0-7") (pin "28") (pinfunction "VCC_28") (pintype "bidirectional"))
      (node (ref "MEMORY_8-15") (pin "26") (pinfunction "CE2_26") (pintype "bidirectional"))
      (node (ref "MEMORY_8-15") (pin "28") (pinfunction "VCC_28") (pintype "bidirectional"))
      (node (ref "RAM_OUT_0-7") (pin "20") (pinfunction "VCC_20") (pintype "bidirectional"))
      (node (ref "RAM_OUT_8-15") (pin "20") (pinfunction "VCC_20") (pintype "bidirectional"))
      (node (ref "S1") (pin "A1") (pinfunction "N.C._1_A1") (pintype "bidirectional"))
    )
    (net (code "102") (name "Net-(AND_GATE-2Y)") (class "Default")
      (node (ref "AND_GATE") (pin "6") (pinfunction "2Y_6") (pintype "bidirectional"))
      (node (ref "BOARD_WRITE") (pin "2") (pinfunction "1A_2") (pintype "bidirectional"))
    )
    (net (code "103") (name "Net-(ARDUINO_WRITE-1A)") (class "Default")
      (node (ref "ARDUINO_WRITE") (pin "2") (pinfunction "1A_2") (pintype "bidirectional"))
      (node (ref "BOARD_WRITE") (pin "4") (pinfunction "1Y_4") (pintype "bidirectional"))
    )
    (net (code "104") (name "Net-(BOARD_WRITE-1B)") (class "Default")
      (node (ref "BOARD_WRITE") (pin "3") (pinfunction "1B_3") (pintype "bidirectional"))
      (node (ref "S1") (pin "A2") (pinfunction "COM_1_A2") (pintype "bidirectional"))
    )
    (net (code "105") (name "Net-(LED0-PadA)") (class "Default")
      (node (ref "LED0") (pin "A") (pinfunction "A_A") (pintype "passive"))
      (node (ref "R0") (pin "1") (pinfunction "1_1") (pintype "passive"))
    )
    (net (code "106") (name "Net-(LED1-PadA)") (class "Default")
      (node (ref "LED1") (pin "A") (pinfunction "A_A") (pintype "passive"))
      (node (ref "R1") (pin "1") (pinfunction "1_1") (pintype "passive"))
    )
    (net (code "107") (name "Net-(LED2-PadA)") (class "Default")
      (node (ref "LED2") (pin "A") (pinfunction "A_A") (pintype "passive"))
      (node (ref "R2") (pin "1") (pinfunction "1_1") (pintype "passive"))
    )
    (net (code "108") (name "Net-(LED3-PadA)") (class "Default")
      (node (ref "LED3") (pin "A") (pinfunction "A_A") (pintype "passive"))
      (node (ref "R3") (pin "1") (pinfunction "1_1") (pintype "passive"))
    )
    (net (code "109") (name "Net-(LED4-PadA)") (class "Default")
      (node (ref "LED4") (pin "A") (pinfunction "A_A") (pintype "passive"))
      (node (ref "R4") (pin "1") (pinfunction "1_1") (pintype "passive"))
    )
    (net (code "110") (name "Net-(LED5-PadA)") (class "Default")
      (node (ref "LED5") (pin "A") (pinfunction "A_A") (pintype "passive"))
      (node (ref "R5") (pin "1") (pinfunction "1_1") (pintype "passive"))
    )
    (net (code "111") (name "Net-(LED6-PadA)") (class "Default")
      (node (ref "LED6") (pin "A") (pinfunction "A_A") (pintype "passive"))
      (node (ref "R6") (pin "1") (pinfunction "1_1") (pintype "passive"))
    )
    (net (code "112") (name "Net-(LED7-PadA)") (class "Default")
      (node (ref "LED7") (pin "A") (pinfunction "A_A") (pintype "passive"))
      (node (ref "R7") (pin "1") (pinfunction "1_1") (pintype "passive"))
    )
    (net (code "113") (name "Net-(LED8-PadA)") (class "Default")
      (node (ref "LED8") (pin "A") (pinfunction "A_A") (pintype "passive"))
      (node (ref "R8") (pin "1") (pinfunction "1_1") (pintype "passive"))
    )
    (net (code "114") (name "Net-(LED9-PadA)") (class "Default")
      (node (ref "LED9") (pin "A") (pinfunction "A_A") (pintype "passive"))
      (node (ref "R9") (pin "1") (pinfunction "1_1") (pintype "passive"))
    )
    (net (code "115") (name "Net-(LED10-PadA)") (class "Default")
      (node (ref "LED10") (pin "A") (pinfunction "A_A") (pintype "passive"))
      (node (ref "R10") (pin "1") (pinfunction "1_1") (pintype "passive"))
    )
    (net (code "116") (name "Net-(LED11-PadA)") (class "Default")
      (node (ref "LED11") (pin "A") (pinfunction "A_A") (pintype "passive"))
      (node (ref "R11") (pin "1") (pinfunction "1_1") (pintype "passive"))
    )
    (net (code "117") (name "Net-(LED12-PadA)") (class "Default")
      (node (ref "LED12") (pin "A") (pinfunction "A_A") (pintype "passive"))
      (node (ref "R12") (pin "1") (pinfunction "1_1") (pintype "passive"))
    )
    (net (code "118") (name "Net-(LED13-PadA)") (class "Default")
      (node (ref "LED13") (pin "A") (pinfunction "A_A") (pintype "passive"))
      (node (ref "R13") (pin "1") (pinfunction "1_1") (pintype "passive"))
    )
    (net (code "119") (name "Net-(LED14-PadA)") (class "Default")
      (node (ref "LED14") (pin "A") (pinfunction "A_A") (pintype "passive"))
      (node (ref "R14") (pin "1") (pinfunction "1_1") (pintype "passive"))
    )
    (net (code "120") (name "Net-(LED15-PadA)") (class "Default")
      (node (ref "LED15") (pin "A") (pinfunction "A_A") (pintype "passive"))
      (node (ref "R15") (pin "1") (pinfunction "1_1") (pintype "passive"))
    )
    (net (code "121") (name "unconnected-(AND_GATE-3Y-Pad8)") (class "Default")
      (node (ref "AND_GATE") (pin "8") (pinfunction "3Y_8") (pintype "bidirectional"))
    )
    (net (code "122") (name "unconnected-(AND_GATE-4Y-Pad11)") (class "Default")
      (node (ref "AND_GATE") (pin "11") (pinfunction "4Y_11") (pintype "bidirectional"))
    )
    (net (code "123") (name "unconnected-(ARDUINO_WRITE-2Y-Pad7)") (class "Default")
      (node (ref "ARDUINO_WRITE") (pin "7") (pinfunction "2Y_7") (pintype "bidirectional"))
    )
    (net (code "124") (name "unconnected-(ARDUINO_WRITE-3Y-Pad9)") (class "Default")
      (node (ref "ARDUINO_WRITE") (pin "9") (pinfunction "3Y_9") (pintype "bidirectional"))
    )
    (net (code "125") (name "unconnected-(ARDUINO_WRITE-4Y-Pad12)") (class "Default")
      (node (ref "ARDUINO_WRITE") (pin "12") (pinfunction "4Y_12") (pintype "bidirectional"))
    )
    (net (code "126") (name "unconnected-(BOARD_WRITE-2Y-Pad7)") (class "Default")
      (node (ref "BOARD_WRITE") (pin "7") (pinfunction "2Y_7") (pintype "bidirectional"))
    )
    (net (code "127") (name "unconnected-(BOARD_WRITE-3Y-Pad9)") (class "Default")
      (node (ref "BOARD_WRITE") (pin "9") (pinfunction "3Y_9") (pintype "bidirectional"))
    )
    (net (code "128") (name "unconnected-(BOARD_WRITE-4Y-Pad12)") (class "Default")
      (node (ref "BOARD_WRITE") (pin "12") (pinfunction "4Y_12") (pintype "bidirectional"))
    )
    (net (code "129") (name "unconnected-(BUS-Pad22)") (class "Default")
      (node (ref "BUS") (pin "22") (pinfunction "22_22") (pintype "bidirectional"))
    )
    (net (code "130") (name "unconnected-(BUS-Pad23)") (class "Default")
      (node (ref "BUS") (pin "23") (pinfunction "23_23") (pintype "bidirectional"))
    )
    (net (code "131") (name "unconnected-(BUS-Pad24)") (class "Default")
      (node (ref "BUS") (pin "24") (pinfunction "24_24") (pintype "bidirectional"))
    )
    (net (code "132") (name "unconnected-(MAR-Pad14)") (class "Default")
      (node (ref "MAR") (pin "14") (pinfunction "14_14") (pintype "bidirectional"))
    )
    (net (code "133") (name "unconnected-(MEMORY_0-7-NC-Pad1)") (class "Default")
      (node (ref "MEMORY_0-7") (pin "1") (pinfunction "NC_1") (pintype "no_connect"))
    )
    (net (code "134") (name "unconnected-(MEMORY_8-15-NC-Pad1)") (class "Default")
      (node (ref "MEMORY_8-15") (pin "1") (pinfunction "NC_1") (pintype "no_connect"))
    )
    (net (code "135") (name "unconnected-(S1-COM_2-PadB2)") (class "Default")
      (node (ref "S1") (pin "B2") (pinfunction "COM_2_B2") (pintype "bidirectional"))
    )
    (net (code "136") (name "unconnected-(S1-N.C._2-PadB1)") (class "Default")
      (node (ref "S1") (pin "B1") (pinfunction "N.C._2_B1") (pintype "bidirectional"))
    )
    (net (code "137") (name "unconnected-(S1-N.O._2-PadB3)") (class "Default")
      (node (ref "S1") (pin "B3") (pinfunction "N.O._2_B3") (pintype "bidirectional"))
    )
  )
)
